# Schematic.net
KiCad netlist of a schematic drawn in Altium Designer
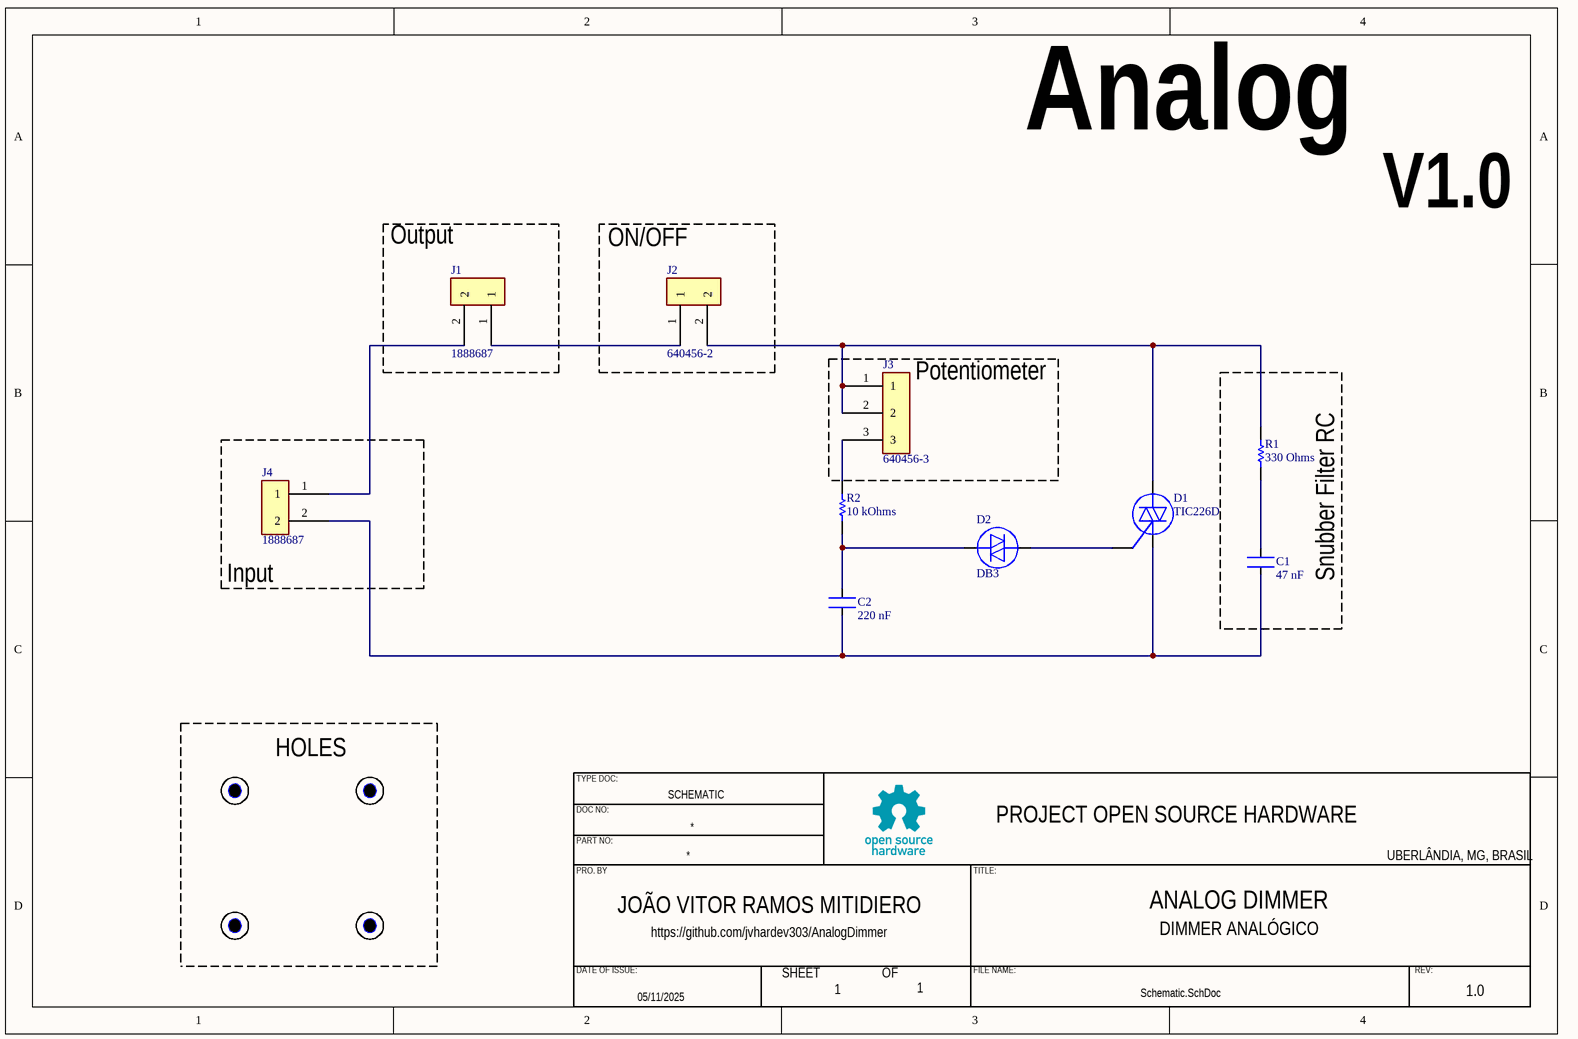
[diagram p0: Schematic.SchDoc]

(export (version "E")
  (design (tool "Eeschema 10.0.6"))
  (components
    (comp (ref "C1")
      (value "47 nF")
      (footprint "CERAMIC_CAPACITOR_GENERIC_PTH")
      (fields (field (name "Comment") "CAPACITOR_N_POL_47nF"))
      (libsource (lib "Simbolos") (part "CAPACITOR_N_POL_47nF"))
    )
    (comp (ref "C2")
      (value "220 nF")
      (footprint "CERAMIC_CAPACITOR_GENERIC_PTH")
      (fields (field (name "Comment") "CAPACITOR_N_POL_220nF"))
      (libsource (lib "Simbolos") (part "CAPACITOR_N_POL_220nF"))
    )
    (comp (ref "D1")
      (value "TRIAC_TIC226D")
      (footprint "TO-220")
      (fields (field (name "PARTNUMBER") "TIC226D"))
      (libsource (lib "Simbolos") (part "TRIAC_TIC226D"))
    )
    (comp (ref "D2")
      (value "DIAC_DB3")
      (footprint "DO-35")
      (fields (field (name "PARTNUMBER") "DB3"))
      (libsource (lib "Simbolos") (part "DIAC_DB3"))
    )
    (comp (ref "HOLE1") (value "FURO_M3") (footprint "FURO_M3") (libsource (lib "Simbolos") (part "FURO_M3")))
    (comp (ref "HOLE2") (value "FURO_M3") (footprint "FURO_M3") (libsource (lib "Simbolos") (part "FURO_M3")))
    (comp (ref "HOLE3") (value "FURO_M3") (footprint "FURO_M3") (libsource (lib "Simbolos") (part "FURO_M3")))
    (comp (ref "HOLE4") (value "FURO_M3") (footprint "FURO_M3") (libsource (lib "Simbolos") (part "FURO_M3")))
    (comp (ref "J1")
      (value "BORNE_2P_1888687")
      (footprint "1888687")
      (fields (field (name "PARTNUMBER") "1888687"))
      (libsource (lib "Simbolos") (part "BORNE_2P_1888687"))
    )
    (comp (ref "J2")
      (value "CONECTOR_2P_640456-2")
      (footprint "640456-2")
      (fields (field (name "PARTNUMBER") "640456-2"))
      (libsource (lib "Simbolos") (part "CONECTOR_2P_640456-2"))
    )
    (comp (ref "J3")
      (value "CONECTOR_3P_640456-3")
      (footprint "640456-3")
      (fields (field (name "PARTNUMBER") "640456-3"))
      (libsource (lib "Simbolos") (part "CONECTOR_3P_640456-3"))
    )
    (comp (ref "J4")
      (value "BORNE_2P_1888687")
      (footprint "1888687")
      (fields (field (name "PARTNUMBER") "1888687"))
      (libsource (lib "") (part "BORNE_2P_1888687_1"))
    )
    (comp (ref "R1")
      (value "330 Ohms")
      (footprint "RESISTOR_1-4_PTH")
      (fields (field (name "Comment") "RESISTOR_330OHMS"))
      (libsource (lib "Simbolos") (part "RESISTOR_330OHMS"))
    )
    (comp (ref "R2")
      (value "10 kOhms")
      (footprint "RESISTOR_1-4_PTH")
      (fields (field (name "Comment") "RESISTOR_10KOHMS"))
      (libsource (lib "Simbolos") (part "RESISTOR_10KOHMS"))
    )
  )
  (nets
    (net (code "1") (name "Net-(C1-Pad1)") (class "Default")
      (node (ref "C1") (pin "1") (pinfunction "1_1") (pintype "passive"))
      (node (ref "R1") (pin "1") (pinfunction "1_1") (pintype "passive"))
    )
    (net (code "2") (name "Net-(C1-Pad2)") (class "Default")
      (node (ref "C1") (pin "2") (pinfunction "2_2") (pintype "passive"))
      (node (ref "C2") (pin "2") (pinfunction "2_2") (pintype "passive"))
      (node (ref "D1") (pin "1") (pinfunction "1_1") (pintype "passive"))
      (node (ref "J4") (pin "2") (pinfunction "2_2") (pintype "passive"))
    )
    (net (code "3") (name "Net-(C2-Pad1)") (class "Default")
      (node (ref "C2") (pin "1") (pinfunction "1_1") (pintype "passive"))
      (node (ref "D2") (pin "1") (pinfunction "1_1") (pintype "passive"))
      (node (ref "R2") (pin "1") (pinfunction "1_1") (pintype "passive"))
    )
    (net (code "4") (name "Net-(D1-Pad2)") (class "Default")
      (node (ref "D1") (pin "2") (pinfunction "2_2") (pintype "passive"))
      (node (ref "J2") (pin "2") (pinfunction "2_2") (pintype "passive"))
      (node (ref "J3") (pin "1") (pinfunction "1_1") (pintype "passive"))
      (node (ref "J3") (pin "2") (pinfunction "2_2") (pintype "passive"))
      (node (ref "R1") (pin "2") (pinfunction "2_2") (pintype "passive"))
    )
    (net (code "5") (name "Net-(D1-Pad3)") (class "Default")
      (node (ref "D1") (pin "3") (pinfunction "3_3") (pintype "passive"))
      (node (ref "D2") (pin "2") (pinfunction "2_2") (pintype "passive"))
    )
    (net (code "6") (name "Net-(J1-Pad1)") (class "Default")
      (node (ref "J1") (pin "1") (pinfunction "1_1") (pintype "passive"))
      (node (ref "J2") (pin "1") (pinfunction "1_1") (pintype "passive"))
    )
    (net (code "7") (name "Net-(J1-Pad2)") (class "Default")
      (node (ref "J1") (pin "2") (pinfunction "2_2") (pintype "passive"))
      (node (ref "J4") (pin "1") (pinfunction "1_1") (pintype "passive"))
    )
    (net (code "8") (name "Net-(J3-Pad3)") (class "Default")
      (node (ref "J3") (pin "3") (pinfunction "3_3") (pintype "passive"))
      (node (ref "R2") (pin "2") (pinfunction "2_2") (pintype "passive"))
    )
  )
)
